# 2021-03-09.net
KiCad netlist of a schematic drawn in EasyEDA
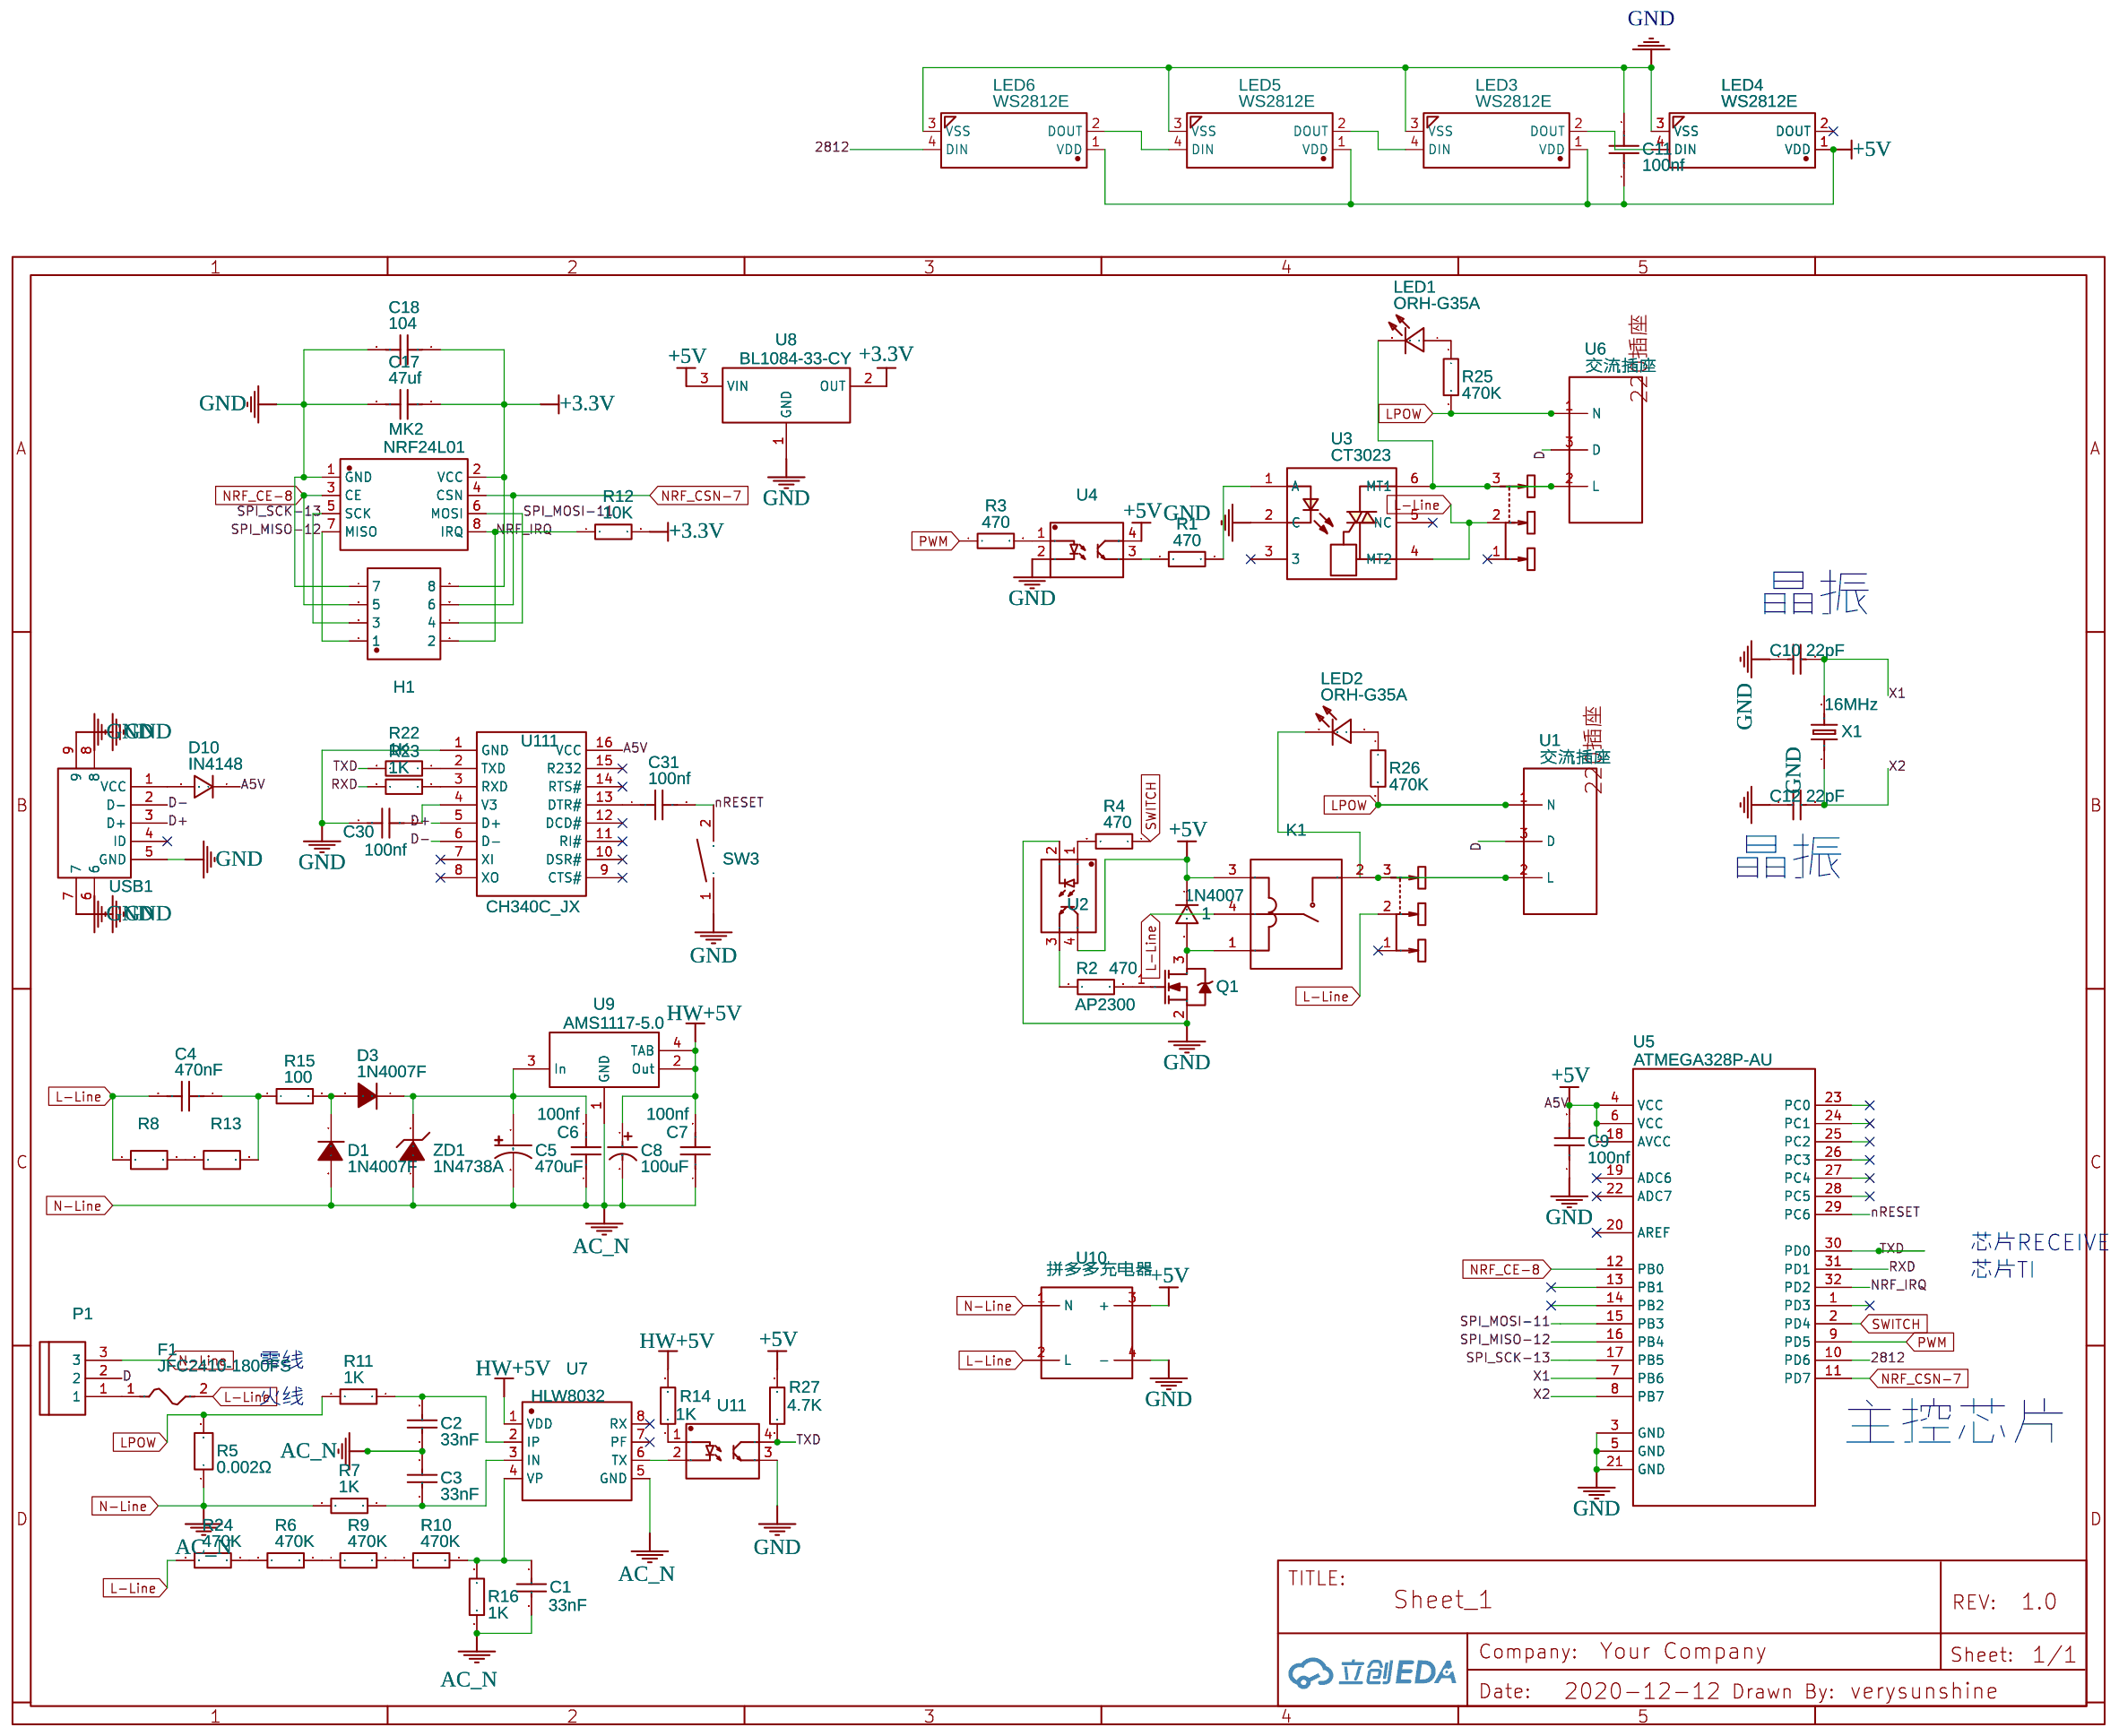
[diagram p0: schematic sheet]

(export (version "E")
  (design (tool "Eeschema 10.0.6"))
  (components
    (comp (ref "1")
      (value "1N4007")
      (fields (field (name "BOM_Supplier Part") "C126233"))
      (libsource (lib "") (part "1N4007_C126233"))
    )
    (comp (ref "C1")
      (value "33nF")
      (fields
        (field (name "BOM_Manufacturer Part") "C2012C0G1H333JT000N")
        (field (name "BOM_Supplier Part") "C76628")
      )
      (libsource (lib "") (part "C2012C0G1H333JT000N"))
    )
    (comp (ref "C2")
      (value "33nF")
      (fields
        (field (name "BOM_Manufacturer Part") "C2012C0G1H333JT000N")
        (field (name "BOM_Supplier Part") "C76628")
      )
      (libsource (lib "") (part "C2012C0G1H333JT000N"))
    )
    (comp (ref "C3")
      (value "33nF")
      (fields
        (field (name "BOM_Manufacturer Part") "C2012C0G1H333JT000N")
        (field (name "BOM_Supplier Part") "C76628")
      )
      (libsource (lib "") (part "C2012C0G1H333JT000N"))
    )
    (comp (ref "C4")
      (value "470nF")
      (fields
        (field (name "BOM_Manufacturer Part") "KP474J2J2001")
        (field (name "BOM_Supplier Part") "C390154")
      )
      (libsource (lib "") (part "KP474J2J2001"))
    )
    (comp (ref "C5")
      (value "470uF")
      (fields
        (field (name "BOM_Manufacturer Part") "LKFD11E471MF")
        (field (name "BOM_Supplier Part") "C270028")
      )
      (libsource (lib "") (part "LKFD11E471MF"))
    )
    (comp (ref "C6") (value "100nf") (libsource (lib "") (part "C_0805_US")))
    (comp (ref "C7") (value "100nf") (libsource (lib "") (part "C_0805_US")))
    (comp (ref "C8")
      (value "100uF")
      (fields
        (field (name "BOM_Manufacturer Part") "100uF 16V 5*7")
        (field (name "BOM_Supplier Part") "C43803")
      )
      (libsource (lib "") (part "100uF 16V 5*7"))
    )
    (comp (ref "C9") (value "100nf") (libsource (lib "") (part "C_0805_US")))
    (comp (ref "C10")
      (value "22pF")
      (fields
        (field (name "BOM_Manufacturer Part") "0402CG220J500NT")
        (field (name "BOM_Supplier Part") "C1555")
      )
      (libsource (lib "") (part "0402CG220J500NT"))
    )
    (comp (ref "C11") (value "100nf") (libsource (lib "") (part "C_0805_US")))
    (comp (ref "C12")
      (value "22pF")
      (fields
        (field (name "BOM_Manufacturer Part") "0402CG220J500NT")
        (field (name "BOM_Supplier Part") "C1555")
      )
      (libsource (lib "") (part "0402CG220J500NT"))
    )
    (comp (ref "C17") (value "47uf") (libsource (lib "") (part "Cap_0603_US")))
    (comp (ref "C18") (value "104") (libsource (lib "") (part "Cap_0603_US")))
    (comp (ref "C30") (value "100nf") (libsource (lib "") (part "C_0805_US_1")))
    (comp (ref "C31") (value "100nf") (libsource (lib "") (part "C_0805_US_1")))
    (comp (ref "D1")
      (value "1N4007F")
      (fields (field (name "BOM_Supplier Part") "C110856"))
      (libsource (lib "") (part "1N4007F_1"))
    )
    (comp (ref "D3")
      (value "1N4007F")
      (fields (field (name "BOM_Supplier Part") "C110856"))
      (libsource (lib "") (part "1N4007F"))
    )
    (comp (ref "D10")
      (value "IN4148")
      (fields (field (name "BOM_Supplier Part") "C14538"))
      (libsource (lib "") (part "IN4148"))
    )
    (comp (ref "F1")
      (value "JFC2410-1800FS")
      (fields (field (name "BOM_Supplier Part") "C136373"))
      (libsource (lib "") (part "JFC2410-1800FS"))
    )
    (comp (ref "H1")
      (value "A2541HWR-2X4P")
      (fields
        (field (name "BOM_Manufacturer Part") "A2541HWR-2x4P")
        (field (name "BOM_Supplier Part") "C239355")
      )
      (libsource (lib "") (part "A2541HWR-2X4P"))
    )
    (comp (ref "K1")
      (value "RD-105DM-A 10A")
      (fields (field (name "BOM_Supplier Part") "C358582"))
      (libsource (lib "") (part "RD-105DM-A 10A"))
    )
    (comp (ref "LED1")
      (value "ORH-G35A")
      (fields (field (name "BOM_Supplier Part") "C205442"))
      (libsource (lib "") (part "ORH-G35A"))
    )
    (comp (ref "LED2")
      (value "ORH-G35A")
      (fields (field (name "BOM_Supplier Part") "C205442"))
      (libsource (lib "") (part "ORH-G35A"))
    )
    (comp (ref "LED3")
      (value "WS2812E")
      (fields (field (name "BOM_Supplier Part") "C139127"))
      (libsource (lib "") (part "WS2812E"))
    )
    (comp (ref "LED4")
      (value "WS2812E")
      (fields (field (name "BOM_Supplier Part") "C139127"))
      (libsource (lib "") (part "WS2812E"))
    )
    (comp (ref "LED5")
      (value "WS2812E")
      (fields (field (name "BOM_Supplier Part") "C139127"))
      (libsource (lib "") (part "WS2812E"))
    )
    (comp (ref "LED6")
      (value "WS2812E")
      (fields (field (name "BOM_Supplier Part") "C139127"))
      (libsource (lib "") (part "WS2812E"))
    )
    (comp (ref "MK2")
      (value "NRF24L01")
      (fields
        (field (name "BOM_Manufacturer Part") "NRF24L01+功率加强版绑定2.4Gwireless module")
        (field (name "BOM_Supplier Part") "C90751")
      )
      (libsource (lib "") (part "NRF24L01"))
    )
    (comp (ref "P1")
      (value "WJ500V-5.08-3P-14-00A")
      (fields (field (name "BOM_Supplier Part") "C72334"))
      (libsource (lib "") (part "WJ500V-5.08-3P-14-00A"))
    )
    (comp (ref "Q1")
      (value "AP2300")
      (fields (field (name "BOM_Supplier Part") "C360338"))
      (libsource (lib "") (part "AP2300"))
    )
    (comp (ref "R1")
      (value "470")
      (fields
        (field (name "BOM_Manufacturer Part") "AC0805JR-07470RL")
        (field (name "BOM_Supplier Part") "C229215")
      )
      (libsource (lib "") (part "AC0805JR-07470RL"))
    )
    (comp (ref "R2")
      (value "470")
      (fields
        (field (name "BOM_Manufacturer Part") "AC0805JR-07470RL")
        (field (name "BOM_Supplier Part") "C229215")
      )
      (libsource (lib "") (part "AC0805JR-07470RL"))
    )
    (comp (ref "R3")
      (value "470")
      (fields
        (field (name "BOM_Manufacturer Part") "AC0805JR-07470RL")
        (field (name "BOM_Supplier Part") "C229215")
      )
      (libsource (lib "") (part "AC0805JR-07470RL"))
    )
    (comp (ref "R4")
      (value "470")
      (fields
        (field (name "BOM_Manufacturer Part") "AC0805JR-07470RL")
        (field (name "BOM_Supplier Part") "C229215")
      )
      (libsource (lib "") (part "AC0805JR-07470RL_1"))
    )
    (comp (ref "R5")
      (value "0.002Ω")
      (fields
        (field (name "BOM_Manufacturer Part") "HolRS3920-3W-2mR-1%")
        (field (name "BOM_Supplier Part") "C558629")
      )
      (libsource (lib "") (part "HOLRS3920-3W-2MR-1%"))
    )
    (comp (ref "R6")
      (value "470K")
      (fields
        (field (name "BOM_Manufacturer Part") "PTFR0805B470KN9")
        (field (name "BOM_Supplier Part") "C351564")
      )
      (libsource (lib "") (part "PTFR0805B470KN9_1"))
    )
    (comp (ref "R7")
      (value "1K")
      (fields
        (field (name "BOM_Manufacturer Part") "AR05BTCW1001")
        (field (name "BOM_Supplier Part") "C316220")
      )
      (libsource (lib "") (part "AR05BTCW1001"))
    )
    (comp (ref "R8")
      (value "RT0805BRE07470KL")
      (fields (field (name "BOM_Supplier Part") "C706280"))
      (libsource (lib "") (part "RT0805BRE07470KL"))
    )
    (comp (ref "R9")
      (value "470K")
      (fields
        (field (name "BOM_Manufacturer Part") "PTFR0805B470KN9")
        (field (name "BOM_Supplier Part") "C351564")
      )
      (libsource (lib "") (part "PTFR0805B470KN9_1"))
    )
    (comp (ref "R10")
      (value "470K")
      (fields
        (field (name "BOM_Manufacturer Part") "PTFR0805B470KN9")
        (field (name "BOM_Supplier Part") "C351564")
      )
      (libsource (lib "") (part "PTFR0805B470KN9_1"))
    )
    (comp (ref "R11")
      (value "1K")
      (fields
        (field (name "BOM_Manufacturer Part") "AR05BTCW1001")
        (field (name "BOM_Supplier Part") "C316220")
      )
      (libsource (lib "") (part "AR05BTCW1001"))
    )
    (comp (ref "R12")
      (value "10K")
      (fields
        (field (name "BOM_Manufacturer Part") "TC0525B1002T5E")
        (field (name "BOM_Supplier Part") "C55866")
      )
      (libsource (lib "") (part "TC0525B1002T5E"))
    )
    (comp (ref "R13")
      (value "RT0805BRE07470KL")
      (fields (field (name "BOM_Supplier Part") "C706280"))
      (libsource (lib "") (part "RT0805BRE07470KL"))
    )
    (comp (ref "R14")
      (value "1K")
      (fields
        (field (name "BOM_Manufacturer Part") "CR0805-FX-1001ELF")
        (field (name "BOM_Supplier Part") "C204136")
      )
      (libsource (lib "") (part "CR0805-FX-1001ELF"))
    )
    (comp (ref "R15")
      (value "100")
      (fields
        (field (name "BOM_Manufacturer Part") "RWS02J1000A520NH")
        (field (name "BOM_Supplier Part") "C275067")
      )
      (libsource (lib "") (part "RWS02J1000A520NH"))
    )
    (comp (ref "R16")
      (value "1K")
      (fields
        (field (name "BOM_Manufacturer Part") "AR05BTCW1001")
        (field (name "BOM_Supplier Part") "C316220")
      )
      (libsource (lib "") (part "AR05BTCW1001_1"))
    )
    (comp (ref "R22")
      (value "1K")
      (fields
        (field (name "BOM_Manufacturer Part") "AR05BTCW1001")
        (field (name "BOM_Supplier Part") "C316220")
      )
      (libsource (lib "") (part "AR05BTCW1001"))
    )
    (comp (ref "R23")
      (value "1K")
      (fields
        (field (name "BOM_Manufacturer Part") "AR05BTCW1001")
        (field (name "BOM_Supplier Part") "C316220")
      )
      (libsource (lib "") (part "AR05BTCW1001"))
    )
    (comp (ref "R24")
      (value "470K")
      (fields
        (field (name "BOM_Manufacturer Part") "PTFR0805B470KN9")
        (field (name "BOM_Supplier Part") "C351564")
      )
      (libsource (lib "") (part "PTFR0805B470KN9_1"))
    )
    (comp (ref "R25")
      (value "470K")
      (fields
        (field (name "BOM_Manufacturer Part") "PTFR0805B470KN9")
        (field (name "BOM_Supplier Part") "C351564")
      )
      (libsource (lib "") (part "PTFR0805B470KN9"))
    )
    (comp (ref "R26")
      (value "470K")
      (fields
        (field (name "BOM_Manufacturer Part") "PTFR0805B470KN9")
        (field (name "BOM_Supplier Part") "C351564")
      )
      (libsource (lib "") (part "PTFR0805B470KN9"))
    )
    (comp (ref "R27")
      (value "4.7K")
      (fields
        (field (name "BOM_Manufacturer Part") "0805W8F1001T5E")
        (field (name "BOM_Supplier Part") "C17513")
      )
      (libsource (lib "") (part "0805W8F1001T5E"))
    )
    (comp (ref "SW2")
      (value "SS-12D10L4")
      (fields (field (name "BOM_Supplier Part") "C843364"))
      (libsource (lib "") (part "SS-12D10L4"))
    )
    (comp (ref "SW3")
      (value "TSA363G25-250B")
      (fields (field (name "BOM_Supplier Part") "C354943"))
      (libsource (lib "") (part "TSA363G25-250B"))
    )
    (comp (ref "SW5")
      (value "SS-12D10L4")
      (fields (field (name "BOM_Supplier Part") "C843364"))
      (libsource (lib "") (part "SS-12D10L4"))
    )
    (comp (ref "U1") (value "交流插座") (libsource (lib "") (part "交流插座")))
    (comp (ref "U2")
      (value "ORPC-817D")
      (fields (field (name "BOM_Supplier Part") "C231231"))
      (libsource (lib "") (part "ORPC-817D"))
    )
    (comp (ref "U3")
      (value "CT3023")
      (fields (field (name "BOM_Supplier Part") "C127192"))
      (libsource (lib "") (part "CT3023"))
    )
    (comp (ref "U4")
      (value "ORPC-817D")
      (fields (field (name "BOM_Supplier Part") "C231231"))
      (libsource (lib "") (part "ORPC-817D_1"))
    )
    (comp (ref "U5")
      (value "ATMEGA328P-AU")
      (fields (field (name "BOM_Supplier Part") "C14877"))
      (libsource (lib "") (part "Unknown_940_-240"))
    )
    (comp (ref "U6") (value "交流插座") (libsource (lib "") (part "交流插座")))
    (comp (ref "U7")
      (value "HLW8032")
      (fields (field (name "BOM_Supplier Part") "C128023"))
      (libsource (lib "") (part "HLW8032"))
    )
    (comp (ref "U8")
      (value "BL1084-33-CY")
      (fields (field (name "BOM_Supplier Part") "C167251"))
      (libsource (lib "") (part "BL1084-33-CY"))
    )
    (comp (ref "U9")
      (value "AMS1117-5.0")
      (fields (field (name "BOM_Supplier Part") "C6187"))
      (libsource (lib "") (part "AMS1117-5.0"))
    )
    (comp (ref "U10") (value "拼多多充电器") (libsource (lib "") (part "拼多多充电器")))
    (comp (ref "U11")
      (value "ORPC-817D")
      (fields (field (name "BOM_Supplier Part") "C231231"))
      (libsource (lib "") (part "ORPC-817D_1"))
    )
    (comp (ref "U111") (value "CH340C_JX") (libsource (lib "") (part "Unknown_285_-525")))
    (comp (ref "USB1")
      (value "U253-051T-4BH87-S-2")
      (fields (field (name "BOM_Supplier Part") "C319173"))
      (libsource (lib "") (part "U253-051T-4BH87-S-2"))
    )
    (comp (ref "X1")
      (value "16MHz")
      (fields
        (field (name "BOM_Manufacturer Part") "XIHCELNANF-16MHZ")
        (field (name "BOM_Supplier Part") "C295075")
      )
      (libsource (lib "") (part "XIHCELNANF-16MHZ"))
    )
    (comp (ref "ZD1")
      (value "1N4738A")
      (fields (field (name "BOM_Supplier Part") "C48508"))
      (libsource (lib "") (part "1N4738A"))
    )
  )
  (nets
    (net (code "1") (name "+3.3V") (class "Default")
      (node (ref "C17") (pin "1") (pinfunction "1_1") (pintype "unspecified"))
      (node (ref "C18") (pin "1") (pinfunction "1_1") (pintype "unspecified"))
      (node (ref "H1") (pin "8") (pinfunction "8_8") (pintype "unspecified"))
      (node (ref "MK2") (pin "2") (pinfunction "VCC_2") (pintype "unspecified"))
      (node (ref "R12") (pin "2") (pinfunction "2_2") (pintype "input"))
      (node (ref "U8") (pin "2") (pinfunction "OUT_2") (pintype "unspecified"))
    )
    (net (code "2") (name "+5V") (class "Default")
      (node (ref "1") (pin "1") (pinfunction "1_1") (pintype "unspecified"))
      (node (ref "C11") (pin "1") (pinfunction "1_1") (pintype "unspecified"))
      (node (ref "C9") (pin "2") (pinfunction "2_2") (pintype "unspecified"))
      (node (ref "D10") (pin "1") (pinfunction "1_1") (pintype "unspecified"))
      (node (ref "K1") (pin "3") (pinfunction "3_3") (pintype "unspecified"))
      (node (ref "LED3") (pin "1") (pinfunction "VDD_1") (pintype "unspecified"))
      (node (ref "LED4") (pin "1") (pinfunction "VDD_1") (pintype "unspecified"))
      (node (ref "LED5") (pin "1") (pinfunction "VDD_1") (pintype "unspecified"))
      (node (ref "LED6") (pin "1") (pinfunction "VDD_1") (pintype "unspecified"))
      (node (ref "R27") (pin "2") (pinfunction "2_2") (pintype "input"))
      (node (ref "U10") (pin "3") (pinfunction "+_3") (pintype "unspecified"))
      (node (ref "U111") (pin "16") (pinfunction "VCC_16") (pintype "unspecified"))
      (node (ref "U2") (pin "4") (pinfunction "C_4") (pintype "unspecified"))
      (node (ref "U4") (pin "4") (pinfunction "C_4") (pintype "unspecified"))
      (node (ref "U5") (pin "18") (pinfunction "AVCC_18") (pintype "passive"))
      (node (ref "U5") (pin "4") (pinfunction "VCC_4") (pintype "passive"))
      (node (ref "U5") (pin "6") (pinfunction "VCC_6") (pintype "passive"))
      (node (ref "U8") (pin "3") (pinfunction "VIN_3") (pintype "unspecified"))
    )
    (net (code "3") (name "/2812") (class "Default")
      (node (ref "LED6") (pin "4") (pinfunction "DIN_4") (pintype "unspecified"))
      (node (ref "U5") (pin "10") (pinfunction "PD6_10") (pintype "unspecified"))
    )
    (net (code "4") (name "/D") (class "Default")
      (node (ref "P1") (pin "2") (pinfunction "2_2") (pintype "unspecified"))
      (node (ref "U1") (pin "3") (pinfunction "D_3") (pintype "unspecified"))
      (node (ref "U6") (pin "3") (pinfunction "D_3") (pintype "unspecified"))
    )
    (net (code "5") (name "/D+") (class "Default")
      (node (ref "U111") (pin "5") (pinfunction "D+_5") (pintype "unspecified"))
      (node (ref "USB1") (pin "3") (pinfunction "D+_3") (pintype "unspecified"))
    )
    (net (code "6") (name "/D-") (class "Default")
      (node (ref "U111") (pin "6") (pinfunction "D-_6") (pintype "unspecified"))
      (node (ref "USB1") (pin "2") (pinfunction "D-_2") (pintype "unspecified"))
    )
    (net (code "7") (name "/NRF_IRQ") (class "Default")
      (node (ref "H1") (pin "2") (pinfunction "2_2") (pintype "unspecified"))
      (node (ref "MK2") (pin "8") (pinfunction "IRQ_8") (pintype "unspecified"))
      (node (ref "R12") (pin "1") (pinfunction "1_1") (pintype "input"))
      (node (ref "U5") (pin "32") (pinfunction "PD2_32") (pintype "unspecified"))
    )
    (net (code "8") (name "/RXD") (class "Default")
      (node (ref "R23") (pin "2") (pinfunction "2_2") (pintype "unspecified"))
      (node (ref "U5") (pin "31") (pinfunction "PD1_31") (pintype "unspecified"))
    )
    (net (code "9") (name "/SPI_MISO-12") (class "Default")
      (node (ref "H1") (pin "1") (pinfunction "1_1") (pintype "unspecified"))
      (node (ref "MK2") (pin "7") (pinfunction "MISO_7") (pintype "unspecified"))
      (node (ref "U5") (pin "16") (pinfunction "PB4_16") (pintype "unspecified"))
    )
    (net (code "10") (name "/SPI_MOSI-11") (class "Default")
      (node (ref "H1") (pin "4") (pinfunction "4_4") (pintype "unspecified"))
      (node (ref "MK2") (pin "6") (pinfunction "MOSI_6") (pintype "unspecified"))
      (node (ref "U5") (pin "15") (pinfunction "PB3_15") (pintype "unspecified"))
    )
    (net (code "11") (name "/SPI_SCK-13") (class "Default")
      (node (ref "H1") (pin "3") (pinfunction "3_3") (pintype "unspecified"))
      (node (ref "MK2") (pin "5") (pinfunction "SCK_5") (pintype "unspecified"))
      (node (ref "U5") (pin "17") (pinfunction "PB5_17") (pintype "unspecified"))
    )
    (net (code "12") (name "/TXD") (class "Default")
      (node (ref "R22") (pin "2") (pinfunction "2_2") (pintype "unspecified"))
      (node (ref "R27") (pin "1") (pinfunction "1_1") (pintype "input"))
      (node (ref "U11") (pin "4") (pinfunction "C_4") (pintype "unspecified"))
      (node (ref "U5") (pin "30") (pinfunction "PD0_30") (pintype "unspecified"))
    )
    (net (code "13") (name "/X1") (class "Default")
      (node (ref "C10") (pin "2") (pinfunction "2_2") (pintype "input"))
      (node (ref "U5") (pin "7") (pinfunction "PB6_7") (pintype "unspecified"))
      (node (ref "X1") (pin "2") (pinfunction "2_2") (pintype "unspecified"))
    )
    (net (code "14") (name "/X2") (class "Default")
      (node (ref "C12") (pin "2") (pinfunction "2_2") (pintype "input"))
      (node (ref "U5") (pin "8") (pinfunction "PB7_8") (pintype "unspecified"))
      (node (ref "X1") (pin "1") (pinfunction "1_1") (pintype "unspecified"))
    )
    (net (code "15") (name "/nRESET") (class "Default")
      (node (ref "C31") (pin "2") (pinfunction "2_2") (pintype "unspecified"))
      (node (ref "SW3") (pin "2") (pinfunction "2_2") (pintype "input"))
      (node (ref "U5") (pin "29") (pinfunction "PC6_29") (pintype "unspecified"))
    )
    (net (code "16") (name "GND") (class "Default")
      (node (ref "C10") (pin "1") (pinfunction "1_1") (pintype "input"))
      (node (ref "C11") (pin "2") (pinfunction "2_2") (pintype "unspecified"))
      (node (ref "C12") (pin "1") (pinfunction "1_1") (pintype "input"))
      (node (ref "C17") (pin "2") (pinfunction "2_2") (pintype "unspecified"))
      (node (ref "C18") (pin "2") (pinfunction "2_2") (pintype "unspecified"))
      (node (ref "C30") (pin "1") (pinfunction "1_1") (pintype "unspecified"))
      (node (ref "C9") (pin "1") (pinfunction "1_1") (pintype "unspecified"))
      (node (ref "H1") (pin "7") (pinfunction "7_7") (pintype "unspecified"))
      (node (ref "LED3") (pin "3") (pinfunction "VSS_3") (pintype "unspecified"))
      (node (ref "LED4") (pin "3") (pinfunction "VSS_3") (pintype "unspecified"))
      (node (ref "LED5") (pin "3") (pinfunction "VSS_3") (pintype "unspecified"))
      (node (ref "LED6") (pin "3") (pinfunction "VSS_3") (pintype "unspecified"))
      (node (ref "MK2") (pin "1") (pinfunction "GND_1") (pintype "unspecified"))
      (node (ref "Q1") (pin "2") (pinfunction "S_2") (pintype "unspecified"))
      (node (ref "SW3") (pin "1") (pinfunction "1_1") (pintype "input"))
      (node (ref "U10") (pin "4") (pinfunction "-_4") (pintype "unspecified"))
      (node (ref "U11") (pin "3") (pinfunction "E_3") (pintype "unspecified"))
      (node (ref "U111") (pin "1") (pinfunction "GND_1") (pintype "unspecified"))
      (node (ref "U2") (pin "2") (pinfunction "C_2") (pintype "unspecified"))
      (node (ref "U3") (pin "2") (pinfunction "C_2") (pintype "unspecified"))
      (node (ref "U4") (pin "2") (pinfunction "C_2") (pintype "unspecified"))
      (node (ref "U5") (pin "21") (pinfunction "GND_21") (pintype "unspecified"))
      (node (ref "U5") (pin "3") (pinfunction "GND_3") (pintype "unspecified"))
      (node (ref "U5") (pin "5") (pinfunction "GND_5") (pintype "unspecified"))
      (node (ref "U8") (pin "1") (pinfunction "GND_1") (pintype "unspecified"))
      (node (ref "USB1") (pin "5") (pinfunction "GND_5") (pintype "unspecified"))
      (node (ref "USB1") (pin "6") (pinfunction "6_6") (pintype "unspecified"))
      (node (ref "USB1") (pin "7") (pinfunction "7_7") (pintype "unspecified"))
      (node (ref "USB1") (pin "8") (pinfunction "8_8") (pintype "unspecified"))
      (node (ref "USB1") (pin "9") (pinfunction "9_9") (pintype "unspecified"))
    )
    (net (code "17") (name "HW+5V") (class "Default")
      (node (ref "C7") (pin "2") (pinfunction "2_2") (pintype "unspecified"))
      (node (ref "C8") (pin "1") (pinfunction "1_1") (pintype "input"))
      (node (ref "R14") (pin "2") (pinfunction "2_2") (pintype "unspecified"))
      (node (ref "U7") (pin "1") (pinfunction "VDD_1") (pintype "unspecified"))
      (node (ref "U9") (pin "2") (pinfunction "Out_2") (pintype "unspecified"))
      (node (ref "U9") (pin "4") (pinfunction "TAB_4") (pintype "unspecified"))
    )
    (net (code "18") (name "L-Line") (class "Default")
      (node (ref "C4") (pin "2") (pinfunction "2_2") (pintype "unspecified"))
      (node (ref "F1") (pin "2") (pinfunction "2_2") (pintype "unspecified"))
      (node (ref "K1") (pin "4") (pinfunction "4_4") (pintype "unspecified"))
      (node (ref "R24") (pin "1") (pinfunction "1_1") (pintype "unspecified"))
      (node (ref "R8") (pin "1") (pinfunction "1_1") (pintype "unspecified"))
      (node (ref "SW2") (pin "2") (pinfunction "2_2") (pintype "unspecified"))
      (node (ref "SW5") (pin "2") (pinfunction "2_2") (pintype "unspecified"))
      (node (ref "U10") (pin "2") (pinfunction "L_2") (pintype "unspecified"))
      (node (ref "U3") (pin "4") (pinfunction "MT2_4") (pintype "unspecified"))
    )
    (net (code "19") (name "LPOW") (class "Default")
      (node (ref "R11") (pin "2") (pinfunction "2_2") (pintype "unspecified"))
      (node (ref "R25") (pin "2") (pinfunction "2_2") (pintype "unspecified"))
      (node (ref "R26") (pin "2") (pinfunction "2_2") (pintype "unspecified"))
      (node (ref "R5") (pin "2") (pinfunction "2_2") (pintype "unspecified"))
      (node (ref "U1") (pin "1") (pinfunction "N_1") (pintype "unspecified"))
      (node (ref "U6") (pin "1") (pinfunction "N_1") (pintype "unspecified"))
    )
    (net (code "20") (name "N-Line") (class "Default")
      (node (ref "C1") (pin "1") (pinfunction "1_1") (pintype "input"))
      (node (ref "C2") (pin "1") (pinfunction "1_1") (pintype "input"))
      (node (ref "C3") (pin "2") (pinfunction "2_2") (pintype "input"))
      (node (ref "C5") (pin "2") (pinfunction "2_2") (pintype "unspecified"))
      (node (ref "C6") (pin "1") (pinfunction "1_1") (pintype "unspecified"))
      (node (ref "C7") (pin "1") (pinfunction "1_1") (pintype "unspecified"))
      (node (ref "C8") (pin "2") (pinfunction "2_2") (pintype "input"))
      (node (ref "D1") (pin "2") (pinfunction "A_2") (pintype "unspecified"))
      (node (ref "P1") (pin "3") (pinfunction "3_3") (pintype "unspecified"))
      (node (ref "R16") (pin "1") (pinfunction "1_1") (pintype "unspecified"))
      (node (ref "R5") (pin "1") (pinfunction "1_1") (pintype "unspecified"))
      (node (ref "R7") (pin "2") (pinfunction "2_2") (pintype "unspecified"))
      (node (ref "U10") (pin "1") (pinfunction "N_1") (pintype "unspecified"))
      (node (ref "U7") (pin "5") (pinfunction "GND_5") (pintype "unspecified"))
      (node (ref "U9") (pin "1") (pinfunction "GND_1") (pintype "unspecified"))
      (node (ref "ZD1") (pin "1") (pinfunction "A_1") (pintype "unspecified"))
    )
    (net (code "21") (name "NRF_CE-8") (class "Default")
      (node (ref "H1") (pin "5") (pinfunction "5_5") (pintype "unspecified"))
      (node (ref "MK2") (pin "3") (pinfunction "CE_3") (pintype "unspecified"))
      (node (ref "U5") (pin "12") (pinfunction "PB0_12") (pintype "unspecified"))
    )
    (net (code "22") (name "NRF_CSN-7") (class "Default")
      (node (ref "H1") (pin "6") (pinfunction "6_6") (pintype "unspecified"))
      (node (ref "MK2") (pin "4") (pinfunction "CSN_4") (pintype "unspecified"))
      (node (ref "U5") (pin "11") (pinfunction "PD7_11") (pintype "unspecified"))
    )
    (net (code "23") (name "Net-(C4-Pad1)") (class "Default")
      (node (ref "C4") (pin "1") (pinfunction "1_1") (pintype "unspecified"))
      (node (ref "R13") (pin "2") (pinfunction "2_2") (pintype "unspecified"))
      (node (ref "R15") (pin "1") (pinfunction "1_1") (pintype "unspecified"))
    )
    (net (code "24") (name "Net-(D1-C)") (class "Default")
      (node (ref "D1") (pin "1") (pinfunction "C_1") (pintype "unspecified"))
      (node (ref "D3") (pin "2") (pinfunction "A_2") (pintype "unspecified"))
      (node (ref "R15") (pin "2") (pinfunction "2_2") (pintype "unspecified"))
    )
    (net (code "25") (name "Net-(D3-C)") (class "Default")
      (node (ref "C5") (pin "1") (pinfunction "1_1") (pintype "unspecified"))
      (node (ref "C6") (pin "2") (pinfunction "2_2") (pintype "unspecified"))
      (node (ref "D3") (pin "1") (pinfunction "C_1") (pintype "unspecified"))
      (node (ref "U9") (pin "3") (pinfunction "In_3") (pintype "unspecified"))
      (node (ref "ZD1") (pin "2") (pinfunction "K_2") (pintype "unspecified"))
    )
    (net (code "26") (name "Net-(F1-Pad1)") (class "Default")
      (node (ref "F1") (pin "1") (pinfunction "1_1") (pintype "unspecified"))
      (node (ref "P1") (pin "1") (pinfunction "1_1") (pintype "unspecified"))
    )
    (net (code "27") (name "Net-(LED1-A)") (class "Default")
      (node (ref "LED1") (pin "1") (pinfunction "A_1") (pintype "unspecified"))
      (node (ref "R25") (pin "1") (pinfunction "1_1") (pintype "unspecified"))
    )
    (net (code "28") (name "Net-(LED1-C)") (class "Default")
      (node (ref "LED1") (pin "2") (pinfunction "C_2") (pintype "unspecified"))
      (node (ref "SW5") (pin "3") (pinfunction "3_3") (pintype "unspecified"))
      (node (ref "U3") (pin "6") (pinfunction "MT1_6") (pintype "unspecified"))
      (node (ref "U6") (pin "2") (pinfunction "L_2") (pintype "unspecified"))
    )
    (net (code "29") (name "Net-(LED2-A)") (class "Default")
      (node (ref "LED2") (pin "1") (pinfunction "A_1") (pintype "unspecified"))
      (node (ref "R26") (pin "1") (pinfunction "1_1") (pintype "unspecified"))
    )
    (net (code "30") (name "Net-(LED2-C)") (class "Default")
      (node (ref "K1") (pin "2") (pinfunction "2_2") (pintype "unspecified"))
      (node (ref "LED2") (pin "2") (pinfunction "C_2") (pintype "unspecified"))
      (node (ref "SW2") (pin "3") (pinfunction "3_3") (pintype "unspecified"))
      (node (ref "U1") (pin "2") (pinfunction "L_2") (pintype "unspecified"))
    )
    (net (code "31") (name "Net-(LED3-DIN)") (class "Default")
      (node (ref "LED3") (pin "4") (pinfunction "DIN_4") (pintype "unspecified"))
      (node (ref "LED5") (pin "2") (pinfunction "DOUT_2") (pintype "unspecified"))
    )
    (net (code "32") (name "Net-(LED3-DOUT)") (class "Default")
      (node (ref "LED3") (pin "2") (pinfunction "DOUT_2") (pintype "unspecified"))
      (node (ref "LED4") (pin "4") (pinfunction "DIN_4") (pintype "unspecified"))
    )
    (net (code "33") (name "Net-(LED5-DIN)") (class "Default")
      (node (ref "LED5") (pin "4") (pinfunction "DIN_4") (pintype "unspecified"))
      (node (ref "LED6") (pin "2") (pinfunction "DOUT_2") (pintype "unspecified"))
    )
    (net (code "34") (name "Net-(Q1-D)") (class "Default")
      (node (ref "1") (pin "2") (pinfunction "2_2") (pintype "unspecified"))
      (node (ref "K1") (pin "1") (pinfunction "1_1") (pintype "unspecified"))
      (node (ref "Q1") (pin "3") (pinfunction "D_3") (pintype "unspecified"))
    )
    (net (code "35") (name "Net-(Q1-G)") (class "Default")
      (node (ref "Q1") (pin "1") (pinfunction "G_1") (pintype "unspecified"))
      (node (ref "R2") (pin "2") (pinfunction "2_2") (pintype "unspecified"))
    )
    (net (code "36") (name "Net-(R6-Pad2)") (class "Default")
      (node (ref "R6") (pin "2") (pinfunction "2_2") (pintype "unspecified"))
      (node (ref "R9") (pin "1") (pinfunction "1_1") (pintype "unspecified"))
    )
    (net (code "37") (name "Net-(R10-Pad1)") (class "Default")
      (node (ref "R10") (pin "1") (pinfunction "1_1") (pintype "unspecified"))
      (node (ref "R9") (pin "2") (pinfunction "2_2") (pintype "unspecified"))
    )
    (net (code "38") (name "Net-(R13-Pad1)") (class "Default")
      (node (ref "R13") (pin "1") (pinfunction "1_1") (pintype "unspecified"))
      (node (ref "R8") (pin "2") (pinfunction "2_2") (pintype "unspecified"))
    )
    (net (code "39") (name "Net-(R24-Pad2)") (class "Default")
      (node (ref "R24") (pin "2") (pinfunction "2_2") (pintype "unspecified"))
      (node (ref "R6") (pin "1") (pinfunction "1_1") (pintype "unspecified"))
    )
    (net (code "40") (name "Net-(U2-A)") (class "Default")
      (node (ref "R4") (pin "2") (pinfunction "2_2") (pintype "unspecified"))
      (node (ref "U2") (pin "1") (pinfunction "A_1") (pintype "unspecified"))
    )
    (net (code "41") (name "Net-(U2-E)") (class "Default")
      (node (ref "R2") (pin "1") (pinfunction "1_1") (pintype "unspecified"))
      (node (ref "U2") (pin "3") (pinfunction "E_3") (pintype "unspecified"))
    )
    (net (code "42") (name "Net-(U3-A)") (class "Default")
      (node (ref "R1") (pin "2") (pinfunction "2_2") (pintype "unspecified"))
      (node (ref "U3") (pin "1") (pinfunction "A_1") (pintype "unspecified"))
    )
    (net (code "43") (name "Net-(U4-A)") (class "Default")
      (node (ref "R3") (pin "2") (pinfunction "2_2") (pintype "unspecified"))
      (node (ref "U4") (pin "1") (pinfunction "A_1") (pintype "unspecified"))
    )
    (net (code "44") (name "Net-(U4-E)") (class "Default")
      (node (ref "R1") (pin "1") (pinfunction "1_1") (pintype "unspecified"))
      (node (ref "U4") (pin "3") (pinfunction "E_3") (pintype "unspecified"))
    )
    (net (code "45") (name "Net-(U7-IN)") (class "Default")
      (node (ref "C3") (pin "1") (pinfunction "1_1") (pintype "input"))
      (node (ref "R7") (pin "1") (pinfunction "1_1") (pintype "unspecified"))
      (node (ref "U7") (pin "3") (pinfunction "IN_3") (pintype "unspecified"))
    )
    (net (code "46") (name "Net-(U7-IP)") (class "Default")
      (node (ref "C2") (pin "2") (pinfunction "2_2") (pintype "input"))
      (node (ref "R11") (pin "1") (pinfunction "1_1") (pintype "unspecified"))
      (node (ref "U7") (pin "2") (pinfunction "IP_2") (pintype "unspecified"))
    )
    (net (code "47") (name "Net-(U7-TX)") (class "Default")
      (node (ref "U11") (pin "2") (pinfunction "C_2") (pintype "unspecified"))
      (node (ref "U7") (pin "6") (pinfunction "TX_6") (pintype "unspecified"))
    )
    (net (code "48") (name "Net-(U7-VP)") (class "Default")
      (node (ref "C1") (pin "2") (pinfunction "2_2") (pintype "input"))
      (node (ref "R10") (pin "2") (pinfunction "2_2") (pintype "unspecified"))
      (node (ref "R16") (pin "2") (pinfunction "2_2") (pintype "unspecified"))
      (node (ref "U7") (pin "4") (pinfunction "VP_4") (pintype "unspecified"))
    )
    (net (code "49") (name "Net-(U11-A)") (class "Default")
      (node (ref "R14") (pin "1") (pinfunction "1_1") (pintype "unspecified"))
      (node (ref "U11") (pin "1") (pinfunction "A_1") (pintype "unspecified"))
    )
    (net (code "50") (name "Net-(U111-DTR#)") (class "Default")
      (node (ref "C31") (pin "1") (pinfunction "1_1") (pintype "unspecified"))
      (node (ref "U111") (pin "13") (pinfunction "DTR#_13") (pintype "unspecified"))
    )
    (net (code "51") (name "Net-(U111-RXD)") (class "Default")
      (node (ref "R23") (pin "1") (pinfunction "1_1") (pintype "unspecified"))
      (node (ref "U111") (pin "3") (pinfunction "RXD_3") (pintype "unspecified"))
    )
    (net (code "52") (name "Net-(U111-TXD)") (class "Default")
      (node (ref "R22") (pin "1") (pinfunction "1_1") (pintype "unspecified"))
      (node (ref "U111") (pin "2") (pinfunction "TXD_2") (pintype "unspecified"))
    )
    (net (code "53") (name "Net-(U111-V3)") (class "Default")
      (node (ref "C30") (pin "2") (pinfunction "2_2") (pintype "unspecified"))
      (node (ref "U111") (pin "4") (pinfunction "V3_4") (pintype "unspecified"))
    )
    (net (code "54") (name "Net-(USB1-VCC)") (class "Default")
      (node (ref "D10") (pin "2") (pinfunction "2_2") (pintype "unspecified"))
      (node (ref "USB1") (pin "1") (pinfunction "VCC_1") (pintype "unspecified"))
    )
    (net (code "55") (name "PWM") (class "Default")
      (node (ref "R3") (pin "1") (pinfunction "1_1") (pintype "unspecified"))
      (node (ref "U5") (pin "9") (pinfunction "PD5_9") (pintype "unspecified"))
    )
    (net (code "56") (name "SWITCH") (class "Default")
      (node (ref "R4") (pin "1") (pinfunction "1_1") (pintype "unspecified"))
      (node (ref "U5") (pin "2") (pinfunction "PD4_2") (pintype "unspecified"))
    )
    (net (code "57") (name "unconnected-(LED4-DOUT-Pad2)") (class "Default")
      (node (ref "LED4") (pin "2") (pinfunction "DOUT_2") (pintype "unspecified+no_connect"))
    )
    (net (code "58") (name "unconnected-(SW2-Pad1)") (class "Default")
      (node (ref "SW2") (pin "1") (pinfunction "1_1") (pintype "unspecified+no_connect"))
    )
    (net (code "59") (name "unconnected-(SW5-Pad1)") (class "Default")
      (node (ref "SW5") (pin "1") (pinfunction "1_1") (pintype "unspecified+no_connect"))
    )
    (net (code "60") (name "unconnected-(U3-NC-Pad5)") (class "Default")
      (node (ref "U3") (pin "5") (pinfunction "NC_5") (pintype "unspecified+no_connect"))
    )
    (net (code "61") (name "unconnected-(U3-Pad3)") (class "Default")
      (node (ref "U3") (pin "3") (pinfunction "3_3") (pintype "unspecified+no_connect"))
    )
    (net (code "62") (name "unconnected-(U5-ADC6-Pad19)") (class "Default")
      (node (ref "U5") (pin "19") (pinfunction "ADC6_19") (pintype "input+no_connect"))
    )
    (net (code "63") (name "unconnected-(U5-ADC7-Pad22)") (class "Default")
      (node (ref "U5") (pin "22") (pinfunction "ADC7_22") (pintype "input+no_connect"))
    )
    (net (code "64") (name "unconnected-(U5-AREF-Pad20)") (class "Default")
      (node (ref "U5") (pin "20") (pinfunction "AREF_20") (pintype "input+no_connect"))
    )
    (net (code "65") (name "unconnected-(U5-PB1-Pad13)") (class "Default")
      (node (ref "U5") (pin "13") (pinfunction "PB1_13") (pintype "unspecified+no_connect"))
    )
    (net (code "66") (name "unconnected-(U5-PB2-Pad14)") (class "Default")
      (node (ref "U5") (pin "14") (pinfunction "PB2_14") (pintype "unspecified+no_connect"))
    )
    (net (code "67") (name "unconnected-(U5-PC0-Pad23)") (class "Default")
      (node (ref "U5") (pin "23") (pinfunction "PC0_23") (pintype "unspecified+no_connect"))
    )
    (net (code "68") (name "unconnected-(U5-PC1-Pad24)") (class "Default")
      (node (ref "U5") (pin "24") (pinfunction "PC1_24") (pintype "unspecified+no_connect"))
    )
    (net (code "69") (name "unconnected-(U5-PC2-Pad25)") (class "Default")
      (node (ref "U5") (pin "25") (pinfunction "PC2_25") (pintype "unspecified+no_connect"))
    )
    (net (code "70") (name "unconnected-(U5-PC3-Pad26)") (class "Default")
      (node (ref "U5") (pin "26") (pinfunction "PC3_26") (pintype "unspecified+no_connect"))
    )
    (net (code "71") (name "unconnected-(U5-PC4-Pad27)") (class "Default")
      (node (ref "U5") (pin "27") (pinfunction "PC4_27") (pintype "unspecified+no_connect"))
    )
    (net (code "72") (name "unconnected-(U5-PC5-Pad28)") (class "Default")
      (node (ref "U5") (pin "28") (pinfunction "PC5_28") (pintype "unspecified+no_connect"))
    )
    (net (code "73") (name "unconnected-(U5-PD3-Pad1)") (class "Default")
      (node (ref "U5") (pin "1") (pinfunction "PD3_1") (pintype "unspecified+no_connect"))
    )
    (net (code "74") (name "unconnected-(U7-PF-Pad7)") (class "Default")
      (node (ref "U7") (pin "7") (pinfunction "PF_7") (pintype "unspecified+no_connect"))
    )
    (net (code "75") (name "unconnected-(U7-RX-Pad8)") (class "Default")
      (node (ref "U7") (pin "8") (pinfunction "RX_8") (pintype "unspecified+no_connect"))
    )
    (net (code "76") (name "unconnected-(U111-CTS#-Pad9)") (class "Default")
      (node (ref "U111") (pin "9") (pinfunction "CTS#_9") (pintype "unspecified+no_connect"))
    )
    (net (code "77") (name "unconnected-(U111-DCD#-Pad12)") (class "Default")
      (node (ref "U111") (pin "12") (pinfunction "DCD#_12") (pintype "unspecified+no_connect"))
    )
    (net (code "78") (name "unconnected-(U111-DSR#-Pad10)") (class "Default")
      (node (ref "U111") (pin "10") (pinfunction "DSR#_10") (pintype "unspecified+no_connect"))
    )
    (net (code "79") (name "unconnected-(U111-R232-Pad15)") (class "Default")
      (node (ref "U111") (pin "15") (pinfunction "R232_15") (pintype "unspecified+no_connect"))
    )
    (net (code "80") (name "unconnected-(U111-RI#-Pad11)") (class "Default")
      (node (ref "U111") (pin "11") (pinfunction "RI#_11") (pintype "unspecified+no_connect"))
    )
    (net (code "81") (name "unconnected-(U111-RTS#-Pad14)") (class "Default")
      (node (ref "U111") (pin "14") (pinfunction "RTS#_14") (pintype "unspecified+no_connect"))
    )
    (net (code "82") (name "unconnected-(U111-XI-Pad7)") (class "Default")
      (node (ref "U111") (pin "7") (pinfunction "XI_7") (pintype "unspecified+no_connect"))
    )
    (net (code "83") (name "unconnected-(U111-XO-Pad8)") (class "Default")
      (node (ref "U111") (pin "8") (pinfunction "XO_8") (pintype "unspecified+no_connect"))
    )
    (net (code "84") (name "unconnected-(USB1-ID-Pad4)") (class "Default")
      (node (ref "USB1") (pin "4") (pinfunction "ID_4") (pintype "unspecified+no_connect"))
    )
  )
)
